# IMU3000.net
KiCad netlist of a schematic drawn in Altium Designer
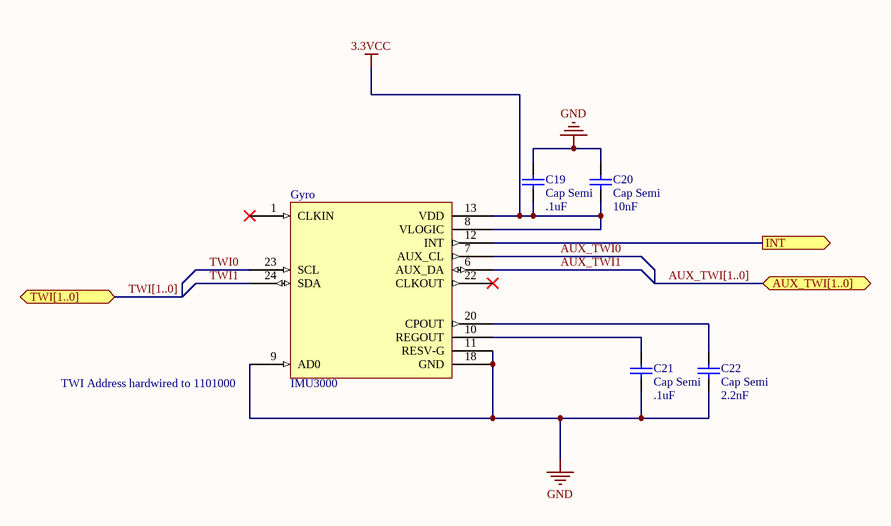
[diagram p0: IMU3000.SchDoc]

(export (version "E")
  (design (tool "Eeschema 10.0.6"))
  (components
    (comp (ref "C19")
      (value "Cap Semi")
      (footprint "CAPC2012N")
      (description "Capacitor (Semiconductor SIM Model)")
      (fields (field (name "ALTIUM_VALUE") ".1uF") (field (name "PUBLISHER") "Altium Limited"))
      (libsource (lib "Miscellaneous Devices") (part "Cap Semi"))
    )
    (comp (ref "C20")
      (value "Cap Semi")
      (footprint "CAPC2012N")
      (description "Capacitor (Semiconductor SIM Model)")
      (fields (field (name "ALTIUM_VALUE") "10nF") (field (name "PUBLISHER") "Altium Limited"))
      (libsource (lib "Miscellaneous Devices") (part "Cap Semi"))
    )
    (comp (ref "C21")
      (value "Cap Semi")
      (footprint "CAPC2012N")
      (description "Capacitor (Semiconductor SIM Model)")
      (fields (field (name "ALTIUM_VALUE") ".1uF") (field (name "PUBLISHER") "Altium Limited"))
      (libsource (lib "Miscellaneous Devices") (part "Cap Semi"))
    )
    (comp (ref "C22")
      (value "Cap Semi")
      (footprint "CAPC2012N")
      (description "Capacitor (Semiconductor SIM Model)")
      (fields (field (name "ALTIUM_VALUE") "2.2nF") (field (name "PUBLISHER") "Altium Limited"))
      (libsource (lib "Miscellaneous Devices") (part "Cap Semi"))
    )
    (comp (ref "Gyro")
      (value "IMU3000")
      (footprint "IMU3000 - ECESHOP")
      (libsource (lib "IMU3000") (part "IMU3000"))
    )
  )
  (nets
    (net (code "1") (name "/AUX_TWI0") (class "Default")
      (node (ref "Gyro") (pin "7") (pinfunction "AUX_CL_7") (pintype "output"))
    )
    (net (code "2") (name "/AUX_TWI1") (class "Default")
      (node (ref "Gyro") (pin "6") (pinfunction "AUX_DA_6") (pintype "bidirectional"))
    )
    (net (code "4") (name "/INT") (class "Default")
      (node (ref "Gyro") (pin "12") (pinfunction "INT_12") (pintype "output"))
    )
    (net (code "5") (name "/TWI0") (class "Default")
      (node (ref "Gyro") (pin "23") (pinfunction "SCL_23") (pintype "input"))
    )
    (net (code "6") (name "/TWI1") (class "Default")
      (node (ref "Gyro") (pin "24") (pinfunction "SDA_24") (pintype "bidirectional"))
    )
    (net (code "8") (name "3.3VCC") (class "Default")
      (node (ref "C19") (pin "2") (pinfunction "2_2") (pintype "passive"))
      (node (ref "C20") (pin "2") (pinfunction "2_2") (pintype "passive"))
      (node (ref "Gyro") (pin "13") (pinfunction "VDD_13") (pintype "power_in"))
      (node (ref "Gyro") (pin "8") (pinfunction "VLOGIC_8") (pintype "passive"))
    )
    (net (code "9") (name "GND") (class "Default")
      (node (ref "C19") (pin "1") (pinfunction "1_1") (pintype "passive"))
      (node (ref "C20") (pin "1") (pinfunction "1_1") (pintype "passive"))
      (node (ref "C21") (pin "1") (pinfunction "1_1") (pintype "passive"))
      (node (ref "C22") (pin "1") (pinfunction "1_1") (pintype "passive"))
      (node (ref "Gyro") (pin "11") (pinfunction "RESV-G_11") (pintype "passive"))
      (node (ref "Gyro") (pin "18") (pinfunction "GND_18") (pintype "passive"))
      (node (ref "Gyro") (pin "9") (pinfunction "AD0_9") (pintype "input"))
    )
    (net (code "10") (name "Net-(Gyro-CPOUT)") (class "Default")
      (node (ref "C22") (pin "2") (pinfunction "2_2") (pintype "passive"))
      (node (ref "Gyro") (pin "20") (pinfunction "CPOUT_20") (pintype "output"))
    )
    (net (code "11") (name "Net-(Gyro-REGOUT)") (class "Default")
      (node (ref "C21") (pin "2") (pinfunction "2_2") (pintype "passive"))
      (node (ref "Gyro") (pin "10") (pinfunction "REGOUT_10") (pintype "passive"))
    )
    (net (code "12") (name "unconnected-(Gyro-CLKIN-Pad1)") (class "Default")
      (node (ref "Gyro") (pin "1") (pinfunction "CLKIN_1") (pintype "input+no_connect"))
    )
    (net (code "13") (name "unconnected-(Gyro-CLKOUT-Pad22)") (class "Default")
      (node (ref "Gyro") (pin "22") (pinfunction "CLKOUT_22") (pintype "output+no_connect"))
    )
  )
)
